# Optocoupler.net
KiCad netlist of a schematic drawn in Altium Designer
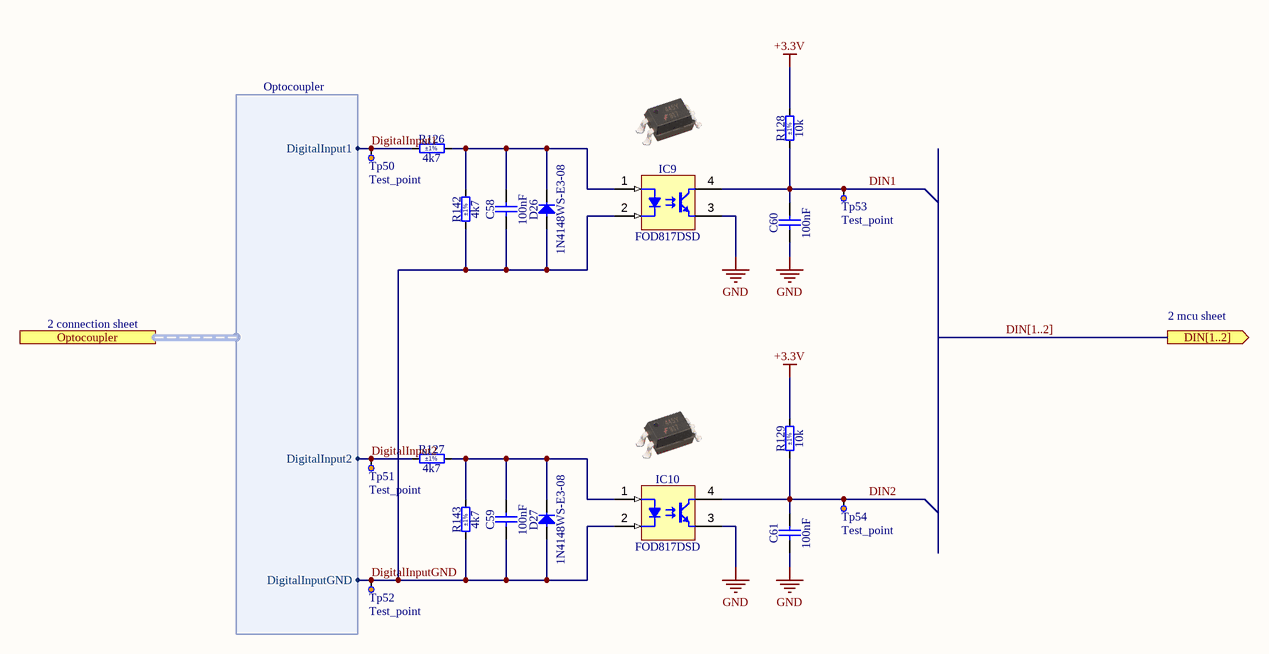
[diagram p0: Optocoupler.SchDoc]

(export (version "E")
  (design (tool "Eeschema 10.0.6"))
  (components
    (comp (ref "C58")
      (value "100nF")
      (footprint "CAPC1608X87N")
      (description "Non-polarised capacitor")
      (fields
        (field (name "PART NUMBER") "CC0603_100NF_50V_10%_X7R")
        (field (name "VOLTAGE") "50V")
        (field (name "AUTHOR") "CERN DEM JLC")
      )
      (libsource (lib "Capacitors") (part "Capacitor - non polarized"))
    )
    (comp (ref "C59")
      (value "100nF")
      (footprint "CAPC1608X87N")
      (description "Non-polarised capacitor")
      (fields
        (field (name "PART NUMBER") "CC0603_100NF_50V_10%_X7R")
        (field (name "VOLTAGE") "50V")
        (field (name "AUTHOR") "CERN DEM JLC")
      )
      (libsource (lib "Capacitors") (part "Capacitor - non polarized"))
    )
    (comp (ref "C60")
      (value "100nF")
      (footprint "CAPC1608X87N")
      (description "Non-polarised capacitor")
      (fields
        (field (name "PART NUMBER") "CC0603_100NF_50V_10%_X7R")
        (field (name "VOLTAGE") "50V")
        (field (name "AUTHOR") "CERN DEM JLC")
      )
      (libsource (lib "Capacitors") (part "Capacitor - non polarized"))
    )
    (comp (ref "C61")
      (value "100nF")
      (footprint "CAPC1608X87N")
      (description "Non-polarised capacitor")
      (fields
        (field (name "PART NUMBER") "CC0603_100NF_50V_10%_X7R")
        (field (name "VOLTAGE") "50V")
        (field (name "AUTHOR") "CERN DEM JLC")
      )
      (libsource (lib "Capacitors") (part "Capacitor - non polarized"))
    )
    (comp (ref "D26")
      (value "1N4148WS-E3-08")
      (footprint "SOD2713X115N")
      (description "Diode")
      (fields
        (field (name "VOLTAGE") "75V")
        (field (name "POWER") "150mA")
        (field (name "AUTHOR") "CERN DEM JLC")
      )
      (libsource (lib "ICs And Semiconductors") (part "Diode"))
    )
    (comp (ref "D27")
      (value "1N4148WS-E3-08")
      (footprint "SOD2713X115N")
      (description "Diode")
      (fields
        (field (name "VOLTAGE") "75V")
        (field (name "POWER") "150mA")
        (field (name "AUTHOR") "CERN DEM JLC")
      )
      (libsource (lib "ICs And Semiconductors") (part "Diode"))
    )
    (comp (ref "IC9")
      (value "FOD817DSD")
      (footprint "FAIRCHILD_FOD817DSD")
      (description "Single Optocoupler")
      (fields (field (name "MANUFACTURER") "FAIRCHILD SEMICONDUCTOR") (field (name "AUTHOR") "CERN DEM JLC"))
      (libsource (lib "ICs And Semiconductors") (part "Optocoupler Type7"))
    )
    (comp (ref "IC10")
      (value "FOD817DSD")
      (footprint "FAIRCHILD_FOD817DSD")
      (description "Single Optocoupler")
      (fields (field (name "MANUFACTURER") "FAIRCHILD SEMICONDUCTOR") (field (name "AUTHOR") "CERN DEM JLC"))
      (libsource (lib "ICs And Semiconductors") (part "Optocoupler Type7"))
    )
    (comp (ref "R126")
      (value "4k7")
      (footprint "RESC6331X70N")
      (description "Resistor - 1%")
      (fields
        (field (name "TOLERANCE") "±1%")
        (field (name "PART NUMBER") "R2512_4K7_1%_1W_100PPM")
        (field (name "POWER") "1W")
        (field (name "AUTHOR") "CERN DEM JLC")
      )
      (libsource (lib "Resistors") (part "Resistor - 1%"))
    )
    (comp (ref "R127")
      (value "4k7")
      (footprint "RESC6331X70N")
      (description "Resistor - 1%")
      (fields
        (field (name "TOLERANCE") "±1%")
        (field (name "PART NUMBER") "R2512_4K7_1%_1W_100PPM")
        (field (name "POWER") "1W")
        (field (name "AUTHOR") "CERN DEM JLC")
      )
      (libsource (lib "Resistors") (part "Resistor - 1%"))
    )
    (comp (ref "R128")
      (value "10k")
      (footprint "RESC1608X55N")
      (description "Resistor - 1%")
      (fields
        (field (name "TOLERANCE") "±1%")
        (field (name "PART NUMBER") "R0603_10K_1%_0.1W_100PPM")
        (field (name "POWER") "0.1W")
        (field (name "AUTHOR") "CERN DEM JLC")
      )
      (libsource (lib "Resistors") (part "Resistor - 1%"))
    )
    (comp (ref "R129")
      (value "10k")
      (footprint "RESC1608X55N")
      (description "Resistor - 1%")
      (fields
        (field (name "TOLERANCE") "±1%")
        (field (name "PART NUMBER") "R0603_10K_1%_0.1W_100PPM")
        (field (name "POWER") "0.1W")
        (field (name "AUTHOR") "CERN DEM JLC")
      )
      (libsource (lib "Resistors") (part "Resistor - 1%"))
    )
    (comp (ref "R142")
      (value "4k7")
      (footprint "RESC1608X55N")
      (description "Resistor - 1%")
      (fields
        (field (name "TOLERANCE") "±1%")
        (field (name "PART NUMBER") "R0603_4K7_1%_0.1W_100PPM")
        (field (name "POWER") "0.1W")
        (field (name "AUTHOR") "CERN DEM JLC")
      )
      (libsource (lib "Resistors") (part "Resistor - 1%"))
    )
    (comp (ref "R143")
      (value "4k7")
      (footprint "RESC1608X55N")
      (description "Resistor - 1%")
      (fields
        (field (name "TOLERANCE") "±1%")
        (field (name "PART NUMBER") "R0603_4K7_1%_0.1W_100PPM")
        (field (name "POWER") "0.1W")
        (field (name "AUTHOR") "CERN DEM JLC")
      )
      (libsource (lib "Resistors") (part "Resistor - 1%"))
    )
    (comp (ref "Tp50")
      (value "Test_point")
      (footprint "fromST:TP_C40")
      (description "Test point")
      (fields (field (name "PUBLISHER") "Altium Limited"))
      (libsource (lib "Sajad_Altium_Library") (part "Test point"))
    )
    (comp (ref "Tp51")
      (value "Test_point")
      (footprint "fromST:TP_C40")
      (description "Test point")
      (fields (field (name "PUBLISHER") "Altium Limited"))
      (libsource (lib "Sajad_Altium_Library") (part "Test point"))
    )
    (comp (ref "Tp52")
      (value "Test_point")
      (footprint "fromST:TP_C40")
      (description "Test point")
      (fields (field (name "PUBLISHER") "Altium Limited"))
      (libsource (lib "Sajad_Altium_Library") (part "Test point"))
    )
    (comp (ref "Tp53")
      (value "Test_point")
      (footprint "fromST:TP_C40")
      (description "Test point")
      (fields (field (name "PUBLISHER") "Altium Limited"))
      (libsource (lib "Sajad_Altium_Library") (part "Test point"))
    )
    (comp (ref "Tp54")
      (value "Test_point")
      (footprint "fromST:TP_C40")
      (description "Test point")
      (fields (field (name "PUBLISHER") "Altium Limited"))
      (libsource (lib "Sajad_Altium_Library") (part "Test point"))
    )
  )
  (nets
    (net (code "2") (name "+3.3V") (class "Default")
      (node (ref "R128") (pin "2") (pinfunction "2_2") (pintype "passive"))
      (node (ref "R129") (pin "2") (pinfunction "2_2") (pintype "passive"))
    )
    (net (code "3") (name "/DIN1") (class "Default")
      (node (ref "C60") (pin "2") (pinfunction "2_2") (pintype "passive"))
      (node (ref "IC9") (pin "4") (pinfunction "C_4") (pintype "open_collector"))
      (node (ref "R128") (pin "1") (pinfunction "1_1") (pintype "passive"))
      (node (ref "Tp53") (pin "1") (pinfunction "1_1") (pintype "passive"))
    )
    (net (code "4") (name "/DIN2") (class "Default")
      (node (ref "C61") (pin "2") (pinfunction "2_2") (pintype "passive"))
      (node (ref "IC10") (pin "4") (pinfunction "C_4") (pintype "open_collector"))
      (node (ref "R129") (pin "1") (pinfunction "1_1") (pintype "passive"))
      (node (ref "Tp54") (pin "1") (pinfunction "1_1") (pintype "passive"))
    )
    (net (code "6") (name "/DigitalInput1") (class "Default")
      (node (ref "R126") (pin "1") (pinfunction "1_1") (pintype "passive"))
      (node (ref "Tp50") (pin "1") (pinfunction "1_1") (pintype "passive"))
    )
    (net (code "7") (name "/DigitalInput2") (class "Default")
      (node (ref "R127") (pin "1") (pinfunction "1_1") (pintype "passive"))
      (node (ref "Tp51") (pin "1") (pinfunction "1_1") (pintype "passive"))
    )
    (net (code "8") (name "/DigitalInputGND") (class "Default")
      (node (ref "C58") (pin "1") (pinfunction "1_1") (pintype "passive"))
      (node (ref "C59") (pin "1") (pinfunction "1_1") (pintype "passive"))
      (node (ref "D26") (pin "2") (pinfunction "A_2") (pintype "passive"))
      (node (ref "D27") (pin "2") (pinfunction "A_2") (pintype "passive"))
      (node (ref "IC10") (pin "2") (pinfunction "C_2") (pintype "input"))
      (node (ref "IC9") (pin "2") (pinfunction "C_2") (pintype "input"))
      (node (ref "R142") (pin "1") (pinfunction "1_1") (pintype "passive"))
      (node (ref "R143") (pin "1") (pinfunction "1_1") (pintype "passive"))
      (node (ref "Tp52") (pin "1") (pinfunction "1_1") (pintype "passive"))
    )
    (net (code "10") (name "GND") (class "Default")
      (node (ref "C60") (pin "1") (pinfunction "1_1") (pintype "passive"))
      (node (ref "C61") (pin "1") (pinfunction "1_1") (pintype "passive"))
      (node (ref "IC10") (pin "3") (pinfunction "E_3") (pintype "passive"))
      (node (ref "IC9") (pin "3") (pinfunction "E_3") (pintype "passive"))
    )
    (net (code "11") (name "Net-(D26-C)") (class "Default")
      (node (ref "C58") (pin "2") (pinfunction "2_2") (pintype "passive"))
      (node (ref "D26") (pin "1") (pinfunction "C_1") (pintype "passive"))
      (node (ref "IC9") (pin "1") (pinfunction "A_1") (pintype "input"))
      (node (ref "R126") (pin "2") (pinfunction "2_2") (pintype "passive"))
      (node (ref "R142") (pin "2") (pinfunction "2_2") (pintype "passive"))
    )
    (net (code "12") (name "Net-(D27-C)") (class "Default")
      (node (ref "C59") (pin "2") (pinfunction "2_2") (pintype "passive"))
      (node (ref "D27") (pin "1") (pinfunction "C_1") (pintype "passive"))
      (node (ref "IC10") (pin "1") (pinfunction "A_1") (pintype "input"))
      (node (ref "R127") (pin "2") (pinfunction "2_2") (pintype "passive"))
      (node (ref "R143") (pin "2") (pinfunction "2_2") (pintype "passive"))
    )
  )
)
